# MCU_PSoC.net
KiCad netlist of a schematic drawn in Altium Designer
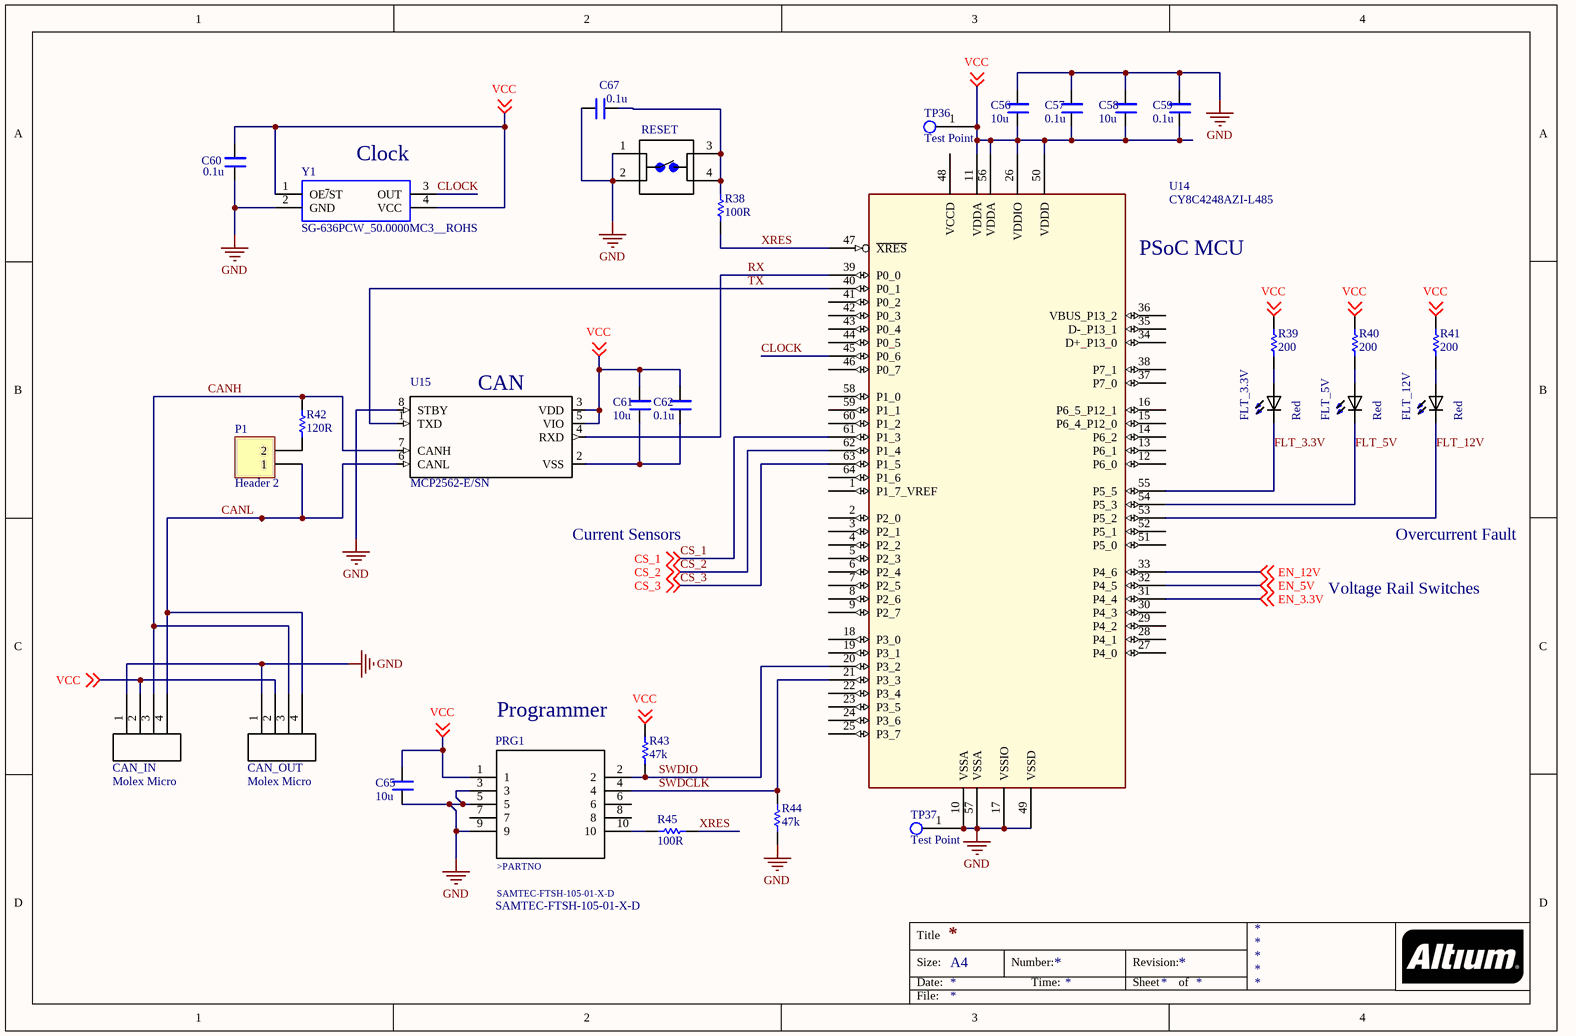
[diagram p0: MCU_PSoC.SchDoc]

(export (version "E")
  (design (tool "Eeschema 10.0.6"))
  (components
    (comp (ref "C56")
      (value "10u")
      (footprint "*CAPC2012X88N")
      (description "100pF Â±5% 250V Ceramic Capacitor C0G, NP0 0805 _2012 Metric_")
      (fields (field (name "MF") "KEMET") (field (name "DIGI-KEY_PART_NUMBER") "399-15000-1-ND"))
      (libsource (lib "C0805C101JAGAC7800") (part "C0805C101JAGAC7800"))
    )
    (comp (ref "C57")
      (value "0.1u")
      (footprint "*CAPC2012X88N")
      (description "100pF Â±5% 250V Ceramic Capacitor C0G, NP0 0805 _2012 Metric_")
      (fields (field (name "MF") "KEMET") (field (name "DIGI-KEY_PART_NUMBER") "399-15000-1-ND"))
      (libsource (lib "C0805C101JAGAC7800") (part "C0805C101JAGAC7800"))
    )
    (comp (ref "C58")
      (value "10u")
      (footprint "*CAPC2012X88N")
      (description "100pF Â±5% 250V Ceramic Capacitor C0G, NP0 0805 _2012 Metric_")
      (fields (field (name "MF") "KEMET") (field (name "DIGI-KEY_PART_NUMBER") "399-15000-1-ND"))
      (libsource (lib "C0805C101JAGAC7800") (part "C0805C101JAGAC7800"))
    )
    (comp (ref "C59")
      (value "0.1u")
      (footprint "*CAPC2012X88N")
      (description "100pF Â±5% 250V Ceramic Capacitor C0G, NP0 0805 _2012 Metric_")
      (fields (field (name "MF") "KEMET") (field (name "DIGI-KEY_PART_NUMBER") "399-15000-1-ND"))
      (libsource (lib "C0805C101JAGAC7800") (part "C0805C101JAGAC7800"))
    )
    (comp (ref "C60")
      (value "0.1u")
      (footprint "*CAPC2012X88N")
      (description "100pF Â±5% 250V Ceramic Capacitor C0G, NP0 0805 _2012 Metric_")
      (fields (field (name "MF") "KEMET") (field (name "DIGI-KEY_PART_NUMBER") "399-15000-1-ND"))
      (libsource (lib "C0805C101JAGAC7800") (part "C0805C101JAGAC7800"))
    )
    (comp (ref "C61")
      (value "10u")
      (footprint "*CAPC2012X88N")
      (description "100pF Â±5% 250V Ceramic Capacitor C0G, NP0 0805 _2012 Metric_")
      (fields (field (name "MF") "KEMET") (field (name "DIGI-KEY_PART_NUMBER") "399-15000-1-ND"))
      (libsource (lib "C0805C101JAGAC7800") (part "C0805C101JAGAC7800"))
    )
    (comp (ref "C62")
      (value "0.1u")
      (footprint "*CAPC2012X88N")
      (description "100pF Â±5% 250V Ceramic Capacitor C0G, NP0 0805 _2012 Metric_")
      (fields (field (name "MF") "KEMET") (field (name "DIGI-KEY_PART_NUMBER") "399-15000-1-ND"))
      (libsource (lib "C0805C101JAGAC7800") (part "C0805C101JAGAC7800"))
    )
    (comp (ref "C65")
      (value "10u")
      (footprint "*CAPC2012X88N")
      (description "100pF Â±5% 250V Ceramic Capacitor C0G, NP0 0805 _2012 Metric_")
      (fields (field (name "MF") "KEMET") (field (name "DIGI-KEY_PART_NUMBER") "399-15000-1-ND"))
      (libsource (lib "C0805C101JAGAC7800") (part "C0805C101JAGAC7800"))
    )
    (comp (ref "C67")
      (value "0.1u")
      (footprint "*CAPC2012X88N")
      (description "100pF Â±5% 250V Ceramic Capacitor C0G, NP0 0805 _2012 Metric_")
      (fields (field (name "MF") "KEMET") (field (name "DIGI-KEY_PART_NUMBER") "399-15000-1-ND"))
      (libsource (lib "C0805C101JAGAC7800") (part "C0805C101JAGAC7800"))
    )
    (comp (ref "CAN_IN")
      (value "Molex Micro")
      (footprint "0430450427")
      (description "Molex micro-fit 3.0 dual row header. P/N 0430450427")
      (libsource (lib "Connector Schematic Symbols") (part "Molex micro-fit 4-pin (Single row schematic)"))
    )
    (comp (ref "CAN_OUT")
      (value "Molex Micro")
      (footprint "0430450427")
      (description "Molex micro-fit 3.0 dual row header. P/N 0430450427")
      (libsource (lib "Connector Schematic Symbols") (part "Molex micro-fit 4-pin (Single row schematic)"))
    )
    (comp (ref "FLT_3.3V")
      (value "Red")
      (footprint "*DIOC200X125X110_LTST-C171KSKT(Primary)")
      (description "Yellow 2 x 1.25 x 0.8 mm 130Â° Water Clear 50 mcd 2 V LED SMT")
      (fields (field (name "MP") "LTST-C171KSKT") (field (name "DIGI-KEY_PART_NUMBER") "160-1428-1-ND"))
      (libsource (lib "LTST-C171KSKT") (part "LTST-C171KSKT"))
    )
    (comp (ref "FLT_5V")
      (value "Red")
      (footprint "*DIOC200X125X110_LTST-C171KSKT(Primary)")
      (description "Yellow 2 x 1.25 x 0.8 mm 130Â° Water Clear 50 mcd 2 V LED SMT")
      (fields (field (name "MP") "LTST-C171KSKT") (field (name "DIGI-KEY_PART_NUMBER") "160-1428-1-ND"))
      (libsource (lib "LTST-C171KSKT") (part "LTST-C171KSKT"))
    )
    (comp (ref "FLT_12V")
      (value "Red")
      (footprint "*DIOC200X125X110_LTST-C171KSKT(Primary)")
      (description "Yellow 2 x 1.25 x 0.8 mm 130Â° Water Clear 50 mcd 2 V LED SMT")
      (fields (field (name "MP") "LTST-C171KSKT") (field (name "DIGI-KEY_PART_NUMBER") "160-1428-1-ND"))
      (libsource (lib "LTST-C171KSKT") (part "LTST-C171KSKT"))
    )
    (comp (ref "P1")
      (value "Header 2")
      (footprint "HDR1X2")
      (description "Header, 2-Pin")
      (fields (field (name "PUBLISHER") "Altium Limited"))
      (libsource (lib "Power Distribution") (part "Header 2"))
    )
    (comp (ref "PRG1")
      (value "SAMTEC-FTSH-105-01-X-D")
      (footprint "SAMTEC-FTSH-105-01-X-D")
      (description "SAMTEC-FTSH-105-01-X-D. Shrouded 10-pin header with .05 in pitch.")
      (libsource (lib "Power Distribution") (part "SAMTEC-FTSH-105-01-X-D"))
    )
    (comp (ref "R38")
      (value "100R")
      (footprint "RESC0805(2012)_M")
      (description "8M06 0.125W 1% 0805 (2012 Metric)  SMD")
      (fields (field (name "POWER") "0.125 W") (field (name "TOLERANCE") "1 %"))
      (libsource (lib "Altium Content Vault") (part "RES"))
    )
    (comp (ref "R39")
      (value "200")
      (footprint "RESC0805(2012)_M")
      (description "8M06 0.125W 1% 0805 (2012 Metric)  SMD")
      (fields (field (name "POWER") "0.125 W") (field (name "TOLERANCE") "1 %"))
      (libsource (lib "Altium Content Vault") (part "RES"))
    )
    (comp (ref "R40")
      (value "200")
      (footprint "RESC0805(2012)_M")
      (description "8M06 0.125W 1% 0805 (2012 Metric)  SMD")
      (fields (field (name "POWER") "0.125 W") (field (name "TOLERANCE") "1 %"))
      (libsource (lib "Altium Content Vault") (part "RES"))
    )
    (comp (ref "R41")
      (value "200")
      (footprint "RESC0805(2012)_M")
      (description "8M06 0.125W 1% 0805 (2012 Metric)  SMD")
      (fields (field (name "POWER") "0.125 W") (field (name "TOLERANCE") "1 %"))
      (libsource (lib "Altium Content Vault") (part "RES"))
    )
    (comp (ref "R42")
      (value "120R")
      (footprint "RESC0805(2012)_N")
      (description "120R 0.125W 5% 0805 (2012 Metric)  SMD")
      (fields (field (name "TOLERANCE") "5 %") (field (name "POWER") "0.125 W"))
      (libsource (lib "CAN Termination Resistor 0805") (part "120R 5% 0805"))
    )
    (comp (ref "R43")
      (value "47k")
      (footprint "RESC0805(2012)_M")
      (description "8M06 0.125W 1% 0805 (2012 Metric)  SMD")
      (fields (field (name "POWER") "0.125 W") (field (name "TOLERANCE") "1 %"))
      (libsource (lib "Altium Content Vault") (part "RES"))
    )
    (comp (ref "R44")
      (value "47k")
      (footprint "RESC0805(2012)_M")
      (description "8M06 0.125W 1% 0805 (2012 Metric)  SMD")
      (fields (field (name "POWER") "0.125 W") (field (name "TOLERANCE") "1 %"))
      (libsource (lib "Altium Content Vault") (part "RES"))
    )
    (comp (ref "R45")
      (value "100R")
      (footprint "RESC0805(2012)_M")
      (description "8M06 0.125W 1% 0805 (2012 Metric)  SMD")
      (fields (field (name "POWER") "0.125 W") (field (name "TOLERANCE") "1 %"))
      (libsource (lib "Altium Content Vault") (part "RES"))
    )
    (comp (ref "RESET")
      (value "1825910-7")
      (footprint "Switch 6mm 24V (NO)")
      (description "FSM4JAH=6MM TACT SWITCH, HIGH TEMP")
      (fields (field (name "MF") "TE Connectivity") (field (name "DIGI-KEY_PART_NUMBER") "450-1804-ND"))
      (libsource (lib "Switch 6mm 24V") (part "Switch 6mm 24V (NO)"))
    )
    (comp (ref "TP36")
      (value "Test Point")
      (footprint "Test Point Through-hole")
      (libsource (lib "Test Points") (part "Test Point"))
    )
    (comp (ref "TP37")
      (value "Test Point")
      (footprint "Test Point Through-hole")
      (libsource (lib "Test Points") (part "Test Point"))
    )
    (comp (ref "U14")
      (value "CY8C4248AZI-L485")
      (footprint "TQFP50P1200X1200X160-64N")
      (libsource (lib "PSOC") (part "CY8C4248AZI-L485"))
    )
    (comp (ref "U15")
      (value "MCP2562-E/SN")
      (footprint "SOIC127P600X175-8N")
      (description "Microchip MCP2562-E/SN, CAN Transceiver 1MBps 1-channel IEC 61000-4-2, 8-Pin SOIC")
      (fields (field (name "MF") "Microchip"))
      (libsource (lib "CAN Tranceiver") (part "MCP2562-E/SN"))
    )
    (comp (ref "Y1")
      (value "SG-636PCW_50.0000MC3__ROHS")
      (footprint "SG-636")
      (description "Standard Clock Oscillators 50MHz 3.3Volt 100ppm -20C +70C")
      (fields (field (name "MANUFACTURER_PART_NUMBER") "SG-636PCW 50.0000MC3: ROHS"))
      (libsource (lib "Oscillator") (part "SG-636"))
    )
  )
  (nets
    (net (code "1") (name "/CANH") (class "Default")
      (node (ref "CAN_IN") (pin "3") (pintype "passive"))
      (node (ref "CAN_OUT") (pin "3") (pintype "passive"))
      (node (ref "R42") (pin "2") (pinfunction "2_2") (pintype "passive"))
      (node (ref "U15") (pin "7") (pinfunction "CANH_7") (pintype "input"))
    )
    (net (code "2") (name "/CANL") (class "Default")
      (node (ref "CAN_IN") (pin "4") (pintype "passive"))
      (node (ref "CAN_OUT") (pin "4") (pintype "passive"))
      (node (ref "P1") (pin "1") (pinfunction "1_1") (pintype "passive"))
      (node (ref "U15") (pin "6") (pinfunction "CANL_6") (pintype "input"))
    )
    (net (code "3") (name "/CLOCK") (class "Default")
      (node (ref "U14") (pin "45") (pinfunction "P0_6_45") (pintype "bidirectional"))
      (node (ref "Y1") (pin "3") (pinfunction "OUT_3") (pintype "passive"))
    )
    (net (code "4") (name "/FLT_3.3V") (class "Default")
      (node (ref "FLT_3.3V") (pin "NEG") (pinfunction "NEG_NEG") (pintype "passive"))
      (node (ref "U14") (pin "55") (pinfunction "P5_5_55") (pintype "bidirectional"))
    )
    (net (code "5") (name "/FLT_5V") (class "Default")
      (node (ref "FLT_5V") (pin "NEG") (pinfunction "NEG_NEG") (pintype "passive"))
      (node (ref "U14") (pin "54") (pinfunction "P5_3_54") (pintype "bidirectional"))
    )
    (net (code "6") (name "/FLT_12V") (class "Default")
      (node (ref "FLT_12V") (pin "NEG") (pinfunction "NEG_NEG") (pintype "passive"))
      (node (ref "U14") (pin "53") (pinfunction "P5_2_53") (pintype "bidirectional"))
    )
    (net (code "7") (name "/RX") (class "Default")
      (node (ref "U14") (pin "39") (pinfunction "P0_0_39") (pintype "bidirectional"))
      (node (ref "U15") (pin "4") (pinfunction "RXD_4") (pintype "output"))
    )
    (net (code "8") (name "/SWDCLK") (class "Default")
      (node (ref "PRG1") (pin "4") (pinfunction "4_4") (pintype "passive"))
      (node (ref "R44") (pin "1") (pinfunction "1_1") (pintype "passive"))
      (node (ref "U14") (pin "21") (pinfunction "P3_3_21") (pintype "bidirectional"))
    )
    (net (code "9") (name "/SWDIO") (class "Default")
      (node (ref "PRG1") (pin "2") (pinfunction "2_2") (pintype "passive"))
      (node (ref "R43") (pin "2") (pinfunction "2_2") (pintype "passive"))
      (node (ref "U14") (pin "20") (pinfunction "P3_2_20") (pintype "bidirectional"))
    )
    (net (code "10") (name "/TX") (class "Default")
      (node (ref "U14") (pin "40") (pinfunction "P0_1_40") (pintype "bidirectional"))
      (node (ref "U15") (pin "1") (pinfunction "TXD_1") (pintype "input"))
    )
    (net (code "11") (name "/XRES") (class "Default")
      (node (ref "R38") (pin "2") (pinfunction "2_2") (pintype "passive"))
      (node (ref "R45") (pin "1") (pinfunction "1_1") (pintype "passive"))
      (node (ref "U14") (pin "47") (pinfunction "~{XRES}_47") (pintype "input"))
    )
    (net (code "12") (name "CS_1") (class "Default")
      (node (ref "U14") (pin "61") (pinfunction "P1_3_61") (pintype "bidirectional"))
    )
    (net (code "13") (name "CS_2") (class "Default")
      (node (ref "U14") (pin "62") (pinfunction "P1_4_62") (pintype "bidirectional"))
    )
    (net (code "14") (name "CS_3") (class "Default")
      (node (ref "U14") (pin "63") (pinfunction "P1_5_63") (pintype "bidirectional"))
    )
    (net (code "15") (name "EN_3.3V") (class "Default")
      (node (ref "U14") (pin "31") (pinfunction "P4_4_31") (pintype "bidirectional"))
    )
    (net (code "16") (name "EN_5V") (class "Default")
      (node (ref "U14") (pin "32") (pinfunction "P4_5_32") (pintype "bidirectional"))
    )
    (net (code "17") (name "EN_12V") (class "Default")
      (node (ref "U14") (pin "33") (pinfunction "P4_6_33") (pintype "bidirectional"))
    )
    (net (code "18") (name "GND") (class "Default")
      (node (ref "C56") (pin "2") (pinfunction "2_2") (pintype "passive"))
      (node (ref "C57") (pin "2") (pinfunction "2_2") (pintype "passive"))
      (node (ref "C58") (pin "2") (pinfunction "2_2") (pintype "passive"))
      (node (ref "C59") (pin "2") (pinfunction "2_2") (pintype "passive"))
      (node (ref "C60") (pin "1") (pinfunction "1_1") (pintype "passive"))
      (node (ref "C65") (pin "1") (pinfunction "1_1") (pintype "passive"))
      (node (ref "C67") (pin "1") (pinfunction "1_1") (pintype "passive"))
      (node (ref "CAN_IN") (pin "1") (pintype "passive"))
      (node (ref "CAN_OUT") (pin "1") (pintype "passive"))
      (node (ref "PRG1") (pin "3") (pinfunction "3_3") (pintype "passive"))
      (node (ref "PRG1") (pin "5") (pinfunction "5_5") (pintype "passive"))
      (node (ref "PRG1") (pin "9") (pinfunction "9_9") (pintype "passive"))
      (node (ref "R44") (pin "2") (pinfunction "2_2") (pintype "passive"))
      (node (ref "RESET") (pin "1") (pinfunction "1_1") (pintype "passive"))
      (node (ref "RESET") (pin "2") (pinfunction "2_2") (pintype "passive"))
      (node (ref "TP37") (pin "1") (pinfunction "1_1") (pintype "passive"))
      (node (ref "U14") (pin "10") (pinfunction "VSSA_10") (pintype "power_in"))
      (node (ref "U14") (pin "17") (pinfunction "VSSIO_17") (pintype "power_in"))
      (node (ref "U14") (pin "49") (pinfunction "VSSD_49") (pintype "power_in"))
      (node (ref "U14") (pin "57") (pinfunction "VSSA_57") (pintype "power_in"))
      (node (ref "U15") (pin "8") (pinfunction "STBY_8") (pintype "input"))
      (node (ref "Y1") (pin "2") (pinfunction "GND_2") (pintype "passive"))
    )
    (net (code "19") (name "Net-(C67-Pad2)") (class "Default")
      (node (ref "C67") (pin "2") (pinfunction "2_2") (pintype "passive"))
      (node (ref "R38") (pin "1") (pinfunction "1_1") (pintype "passive"))
      (node (ref "RESET") (pin "3") (pinfunction "3_3") (pintype "passive"))
      (node (ref "RESET") (pin "4") (pinfunction "4_4") (pintype "passive"))
    )
    (net (code "20") (name "Net-(FLT_3.3V-PadPOS)") (class "Default")
      (node (ref "FLT_3.3V") (pin "POS") (pinfunction "POS_POS") (pintype "passive"))
      (node (ref "R39") (pin "1") (pinfunction "1_1") (pintype "passive"))
    )
    (net (code "21") (name "Net-(FLT_5V-PadPOS)") (class "Default")
      (node (ref "FLT_5V") (pin "POS") (pinfunction "POS_POS") (pintype "passive"))
      (node (ref "R40") (pin "1") (pinfunction "1_1") (pintype "passive"))
    )
    (net (code "22") (name "Net-(FLT_12V-PadPOS)") (class "Default")
      (node (ref "FLT_12V") (pin "POS") (pinfunction "POS_POS") (pintype "passive"))
      (node (ref "R41") (pin "1") (pinfunction "1_1") (pintype "passive"))
    )
    (net (code "23") (name "Net-(P1-Pad2)") (class "Default")
      (node (ref "P1") (pin "2") (pinfunction "2_2") (pintype "passive"))
      (node (ref "R42") (pin "1") (pinfunction "1_1") (pintype "passive"))
    )
    (net (code "24") (name "Net-(PRG1-Pad10)") (class "Default")
      (node (ref "PRG1") (pin "10") (pinfunction "10_10") (pintype "passive"))
      (node (ref "R45") (pin "2") (pinfunction "2_2") (pintype "passive"))
    )
    (net (code "25") (name "Net-(U15-VSS)") (class "Default")
      (node (ref "C61") (pin "1") (pinfunction "1_1") (pintype "passive"))
      (node (ref "C62") (pin "1") (pinfunction "1_1") (pintype "passive"))
      (node (ref "U15") (pin "2") (pinfunction "VSS_2") (pintype "power_in"))
    )
    (net (code "26") (name "VCC") (class "Default")
      (node (ref "C56") (pin "1") (pinfunction "1_1") (pintype "passive"))
      (node (ref "C57") (pin "1") (pinfunction "1_1") (pintype "passive"))
      (node (ref "C58") (pin "1") (pinfunction "1_1") (pintype "passive"))
      (node (ref "C59") (pin "1") (pinfunction "1_1") (pintype "passive"))
      (node (ref "C60") (pin "2") (pinfunction "2_2") (pintype "passive"))
      (node (ref "C61") (pin "2") (pinfunction "2_2") (pintype "passive"))
      (node (ref "C62") (pin "2") (pinfunction "2_2") (pintype "passive"))
      (node (ref "C65") (pin "2") (pinfunction "2_2") (pintype "passive"))
      (node (ref "CAN_IN") (pin "2") (pintype "passive"))
      (node (ref "CAN_OUT") (pin "2") (pintype "passive"))
      (node (ref "PRG1") (pin "1") (pinfunction "1_1") (pintype "passive"))
      (node (ref "R39") (pin "2") (pinfunction "2_2") (pintype "passive"))
      (node (ref "R40") (pin "2") (pinfunction "2_2") (pintype "passive"))
      (node (ref "R41") (pin "2") (pinfunction "2_2") (pintype "passive"))
      (node (ref "R43") (pin "1") (pinfunction "1_1") (pintype "passive"))
      (node (ref "TP36") (pin "1") (pinfunction "1_1") (pintype "passive"))
      (node (ref "U14") (pin "11") (pinfunction "VDDA_11") (pintype "power_in"))
      (node (ref "U14") (pin "26") (pinfunction "VDDIO_26") (pintype "power_in"))
      (node (ref "U14") (pin "50") (pinfunction "VDDD_50") (pintype "power_in"))
      (node (ref "U14") (pin "56") (pinfunction "VDDA_56") (pintype "power_in"))
      (node (ref "U15") (pin "3") (pinfunction "VDD_3") (pintype "power_in"))
      (node (ref "U15") (pin "5") (pinfunction "VIO_5") (pintype "power_in"))
      (node (ref "Y1") (pin "1") (pinfunction "OE~{/}ST_1") (pintype "passive"))
      (node (ref "Y1") (pin "4") (pinfunction "VCC_4") (pintype "power_in"))
    )
    (net (code "27") (name "unconnected-(PRG1-Pad6)") (class "Default")
      (node (ref "PRG1") (pin "6") (pinfunction "6_6") (pintype "passive"))
    )
    (net (code "28") (name "unconnected-(PRG1-Pad7)") (class "Default")
      (node (ref "PRG1") (pin "7") (pinfunction "7_7") (pintype "passive"))
    )
    (net (code "29") (name "unconnected-(PRG1-Pad8)") (class "Default")
      (node (ref "PRG1") (pin "8") (pinfunction "8_8") (pintype "passive"))
    )
    (net (code "30") (name "unconnected-(U14-D+_P13_0-Pad34)") (class "Default")
      (node (ref "U14") (pin "34") (pinfunction "D+_P13_0_34") (pintype "bidirectional"))
    )
    (net (code "31") (name "unconnected-(U14-D-_P13_1-Pad35)") (class "Default")
      (node (ref "U14") (pin "35") (pinfunction "D-_P13_1_35") (pintype "bidirectional"))
    )
    (net (code "32") (name "unconnected-(U14-P0_2-Pad41)") (class "Default")
      (node (ref "U14") (pin "41") (pinfunction "P0_2_41") (pintype "bidirectional"))
    )
    (net (code "33") (name "unconnected-(U14-P0_3-Pad42)") (class "Default")
      (node (ref "U14") (pin "42") (pinfunction "P0_3_42") (pintype "bidirectional"))
    )
    (net (code "34") (name "unconnected-(U14-P0_4-Pad43)") (class "Default")
      (node (ref "U14") (pin "43") (pinfunction "P0_4_43") (pintype "bidirectional"))
    )
    (net (code "35") (name "unconnected-(U14-P0_5-Pad44)") (class "Default")
      (node (ref "U14") (pin "44") (pinfunction "P0_5_44") (pintype "bidirectional"))
    )
    (net (code "36") (name "unconnected-(U14-P0_7-Pad46)") (class "Default")
      (node (ref "U14") (pin "46") (pinfunction "P0_7_46") (pintype "bidirectional"))
    )
    (net (code "37") (name "unconnected-(U14-P1_0-Pad58)") (class "Default")
      (node (ref "U14") (pin "58") (pinfunction "P1_0_58") (pintype "bidirectional"))
    )
    (net (code "38") (name "unconnected-(U14-P1_1-Pad59)") (class "Default")
      (node (ref "U14") (pin "59") (pinfunction "P1_1_59") (pintype "bidirectional"))
    )
    (net (code "39") (name "unconnected-(U14-P1_2-Pad60)") (class "Default")
      (node (ref "U14") (pin "60") (pinfunction "P1_2_60") (pintype "bidirectional"))
    )
    (net (code "40") (name "unconnected-(U14-P1_6-Pad64)") (class "Default")
      (node (ref "U14") (pin "64") (pinfunction "P1_6_64") (pintype "bidirectional"))
    )
    (net (code "41") (name "unconnected-(U14-P1_7_VREF-Pad1)") (class "Default")
      (node (ref "U14") (pin "1") (pinfunction "P1_7_VREF_1") (pintype "bidirectional"))
    )
    (net (code "42") (name "unconnected-(U14-P2_0-Pad2)") (class "Default")
      (node (ref "U14") (pin "2") (pinfunction "P2_0_2") (pintype "bidirectional"))
    )
    (net (code "43") (name "unconnected-(U14-P2_1-Pad3)") (class "Default")
      (node (ref "U14") (pin "3") (pinfunction "P2_1_3") (pintype "bidirectional"))
    )
    (net (code "44") (name "unconnected-(U14-P2_2-Pad4)") (class "Default")
      (node (ref "U14") (pin "4") (pinfunction "P2_2_4") (pintype "bidirectional"))
    )
    (net (code "45") (name "unconnected-(U14-P2_3-Pad5)") (class "Default")
      (node (ref "U14") (pin "5") (pinfunction "P2_3_5") (pintype "bidirectional"))
    )
    (net (code "46") (name "unconnected-(U14-P2_4-Pad6)") (class "Default")
      (node (ref "U14") (pin "6") (pinfunction "P2_4_6") (pintype "bidirectional"))
    )
    (net (code "47") (name "unconnected-(U14-P2_5-Pad7)") (class "Default")
      (node (ref "U14") (pin "7") (pinfunction "P2_5_7") (pintype "bidirectional"))
    )
    (net (code "48") (name "unconnected-(U14-P2_6-Pad8)") (class "Default")
      (node (ref "U14") (pin "8") (pinfunction "P2_6_8") (pintype "bidirectional"))
    )
    (net (code "49") (name "unconnected-(U14-P2_7-Pad9)") (class "Default")
      (node (ref "U14") (pin "9") (pinfunction "P2_7_9") (pintype "bidirectional"))
    )
    (net (code "50") (name "unconnected-(U14-P3_0-Pad18)") (class "Default")
      (node (ref "U14") (pin "18") (pinfunction "P3_0_18") (pintype "bidirectional"))
    )
    (net (code "51") (name "unconnected-(U14-P3_1-Pad19)") (class "Default")
      (node (ref "U14") (pin "19") (pinfunction "P3_1_19") (pintype "bidirectional"))
    )
    (net (code "52") (name "unconnected-(U14-P3_4-Pad22)") (class "Default")
      (node (ref "U14") (pin "22") (pinfunction "P3_4_22") (pintype "bidirectional"))
    )
    (net (code "53") (name "unconnected-(U14-P3_5-Pad23)") (class "Default")
      (node (ref "U14") (pin "23") (pinfunction "P3_5_23") (pintype "bidirectional"))
    )
    (net (code "54") (name "unconnected-(U14-P3_6-Pad24)") (class "Default")
      (node (ref "U14") (pin "24") (pinfunction "P3_6_24") (pintype "bidirectional"))
    )
    (net (code "55") (name "unconnected-(U14-P3_7-Pad25)") (class "Default")
      (node (ref "U14") (pin "25") (pinfunction "P3_7_25") (pintype "bidirectional"))
    )
    (net (code "56") (name "unconnected-(U14-P4_0-Pad27)") (class "Default")
      (node (ref "U14") (pin "27") (pinfunction "P4_0_27") (pintype "bidirectional"))
    )
    (net (code "57") (name "unconnected-(U14-P4_1-Pad28)") (class "Default")
      (node (ref "U14") (pin "28") (pinfunction "P4_1_28") (pintype "bidirectional"))
    )
    (net (code "58") (name "unconnected-(U14-P4_2-Pad29)") (class "Default")
      (node (ref "U14") (pin "29") (pinfunction "P4_2_29") (pintype "bidirectional"))
    )
    (net (code "59") (name "unconnected-(U14-P4_3-Pad30)") (class "Default")
      (node (ref "U14") (pin "30") (pinfunction "P4_3_30") (pintype "bidirectional"))
    )
    (net (code "60") (name "unconnected-(U14-P5_0-Pad51)") (class "Default")
      (node (ref "U14") (pin "51") (pinfunction "P5_0_51") (pintype "bidirectional"))
    )
    (net (code "61") (name "unconnected-(U14-P5_1-Pad52)") (class "Default")
      (node (ref "U14") (pin "52") (pinfunction "P5_1_52") (pintype "bidirectional"))
    )
    (net (code "62") (name "unconnected-(U14-P6_0-Pad12)") (class "Default")
      (node (ref "U14") (pin "12") (pinfunction "P6_0_12") (pintype "bidirectional"))
    )
    (net (code "63") (name "unconnected-(U14-P6_1-Pad13)") (class "Default")
      (node (ref "U14") (pin "13") (pinfunction "P6_1_13") (pintype "bidirectional"))
    )
    (net (code "64") (name "unconnected-(U14-P6_2-Pad14)") (class "Default")
      (node (ref "U14") (pin "14") (pinfunction "P6_2_14") (pintype "bidirectional"))
    )
    (net (code "65") (name "unconnected-(U14-P6_4_P12_0-Pad15)") (class "Default")
      (node (ref "U14") (pin "15") (pinfunction "P6_4_P12_0_15") (pintype "bidirectional"))
    )
    (net (code "66") (name "unconnected-(U14-P6_5_P12_1-Pad16)") (class "Default")
      (node (ref "U14") (pin "16") (pinfunction "P6_5_P12_1_16") (pintype "bidirectional"))
    )
    (net (code "67") (name "unconnected-(U14-P7_0-Pad37)") (class "Default")
      (node (ref "U14") (pin "37") (pinfunction "P7_0_37") (pintype "bidirectional"))
    )
    (net (code "68") (name "unconnected-(U14-P7_1-Pad38)") (class "Default")
      (node (ref "U14") (pin "38") (pinfunction "P7_1_38") (pintype "bidirectional"))
    )
    (net (code "69") (name "unconnected-(U14-VBUS_P13_2-Pad36)") (class "Default")
      (node (ref "U14") (pin "36") (pinfunction "VBUS_P13_2_36") (pintype "bidirectional"))
    )
    (net (code "70") (name "unconnected-(U14-VCCD-Pad48)") (class "Default")
      (node (ref "U14") (pin "48") (pinfunction "VCCD_48") (pintype "power_in"))
    )
  )
)
